# SCH_esp32_sensors_2026-04-30.net
KiCad netlist of a schematic drawn in EasyEDA
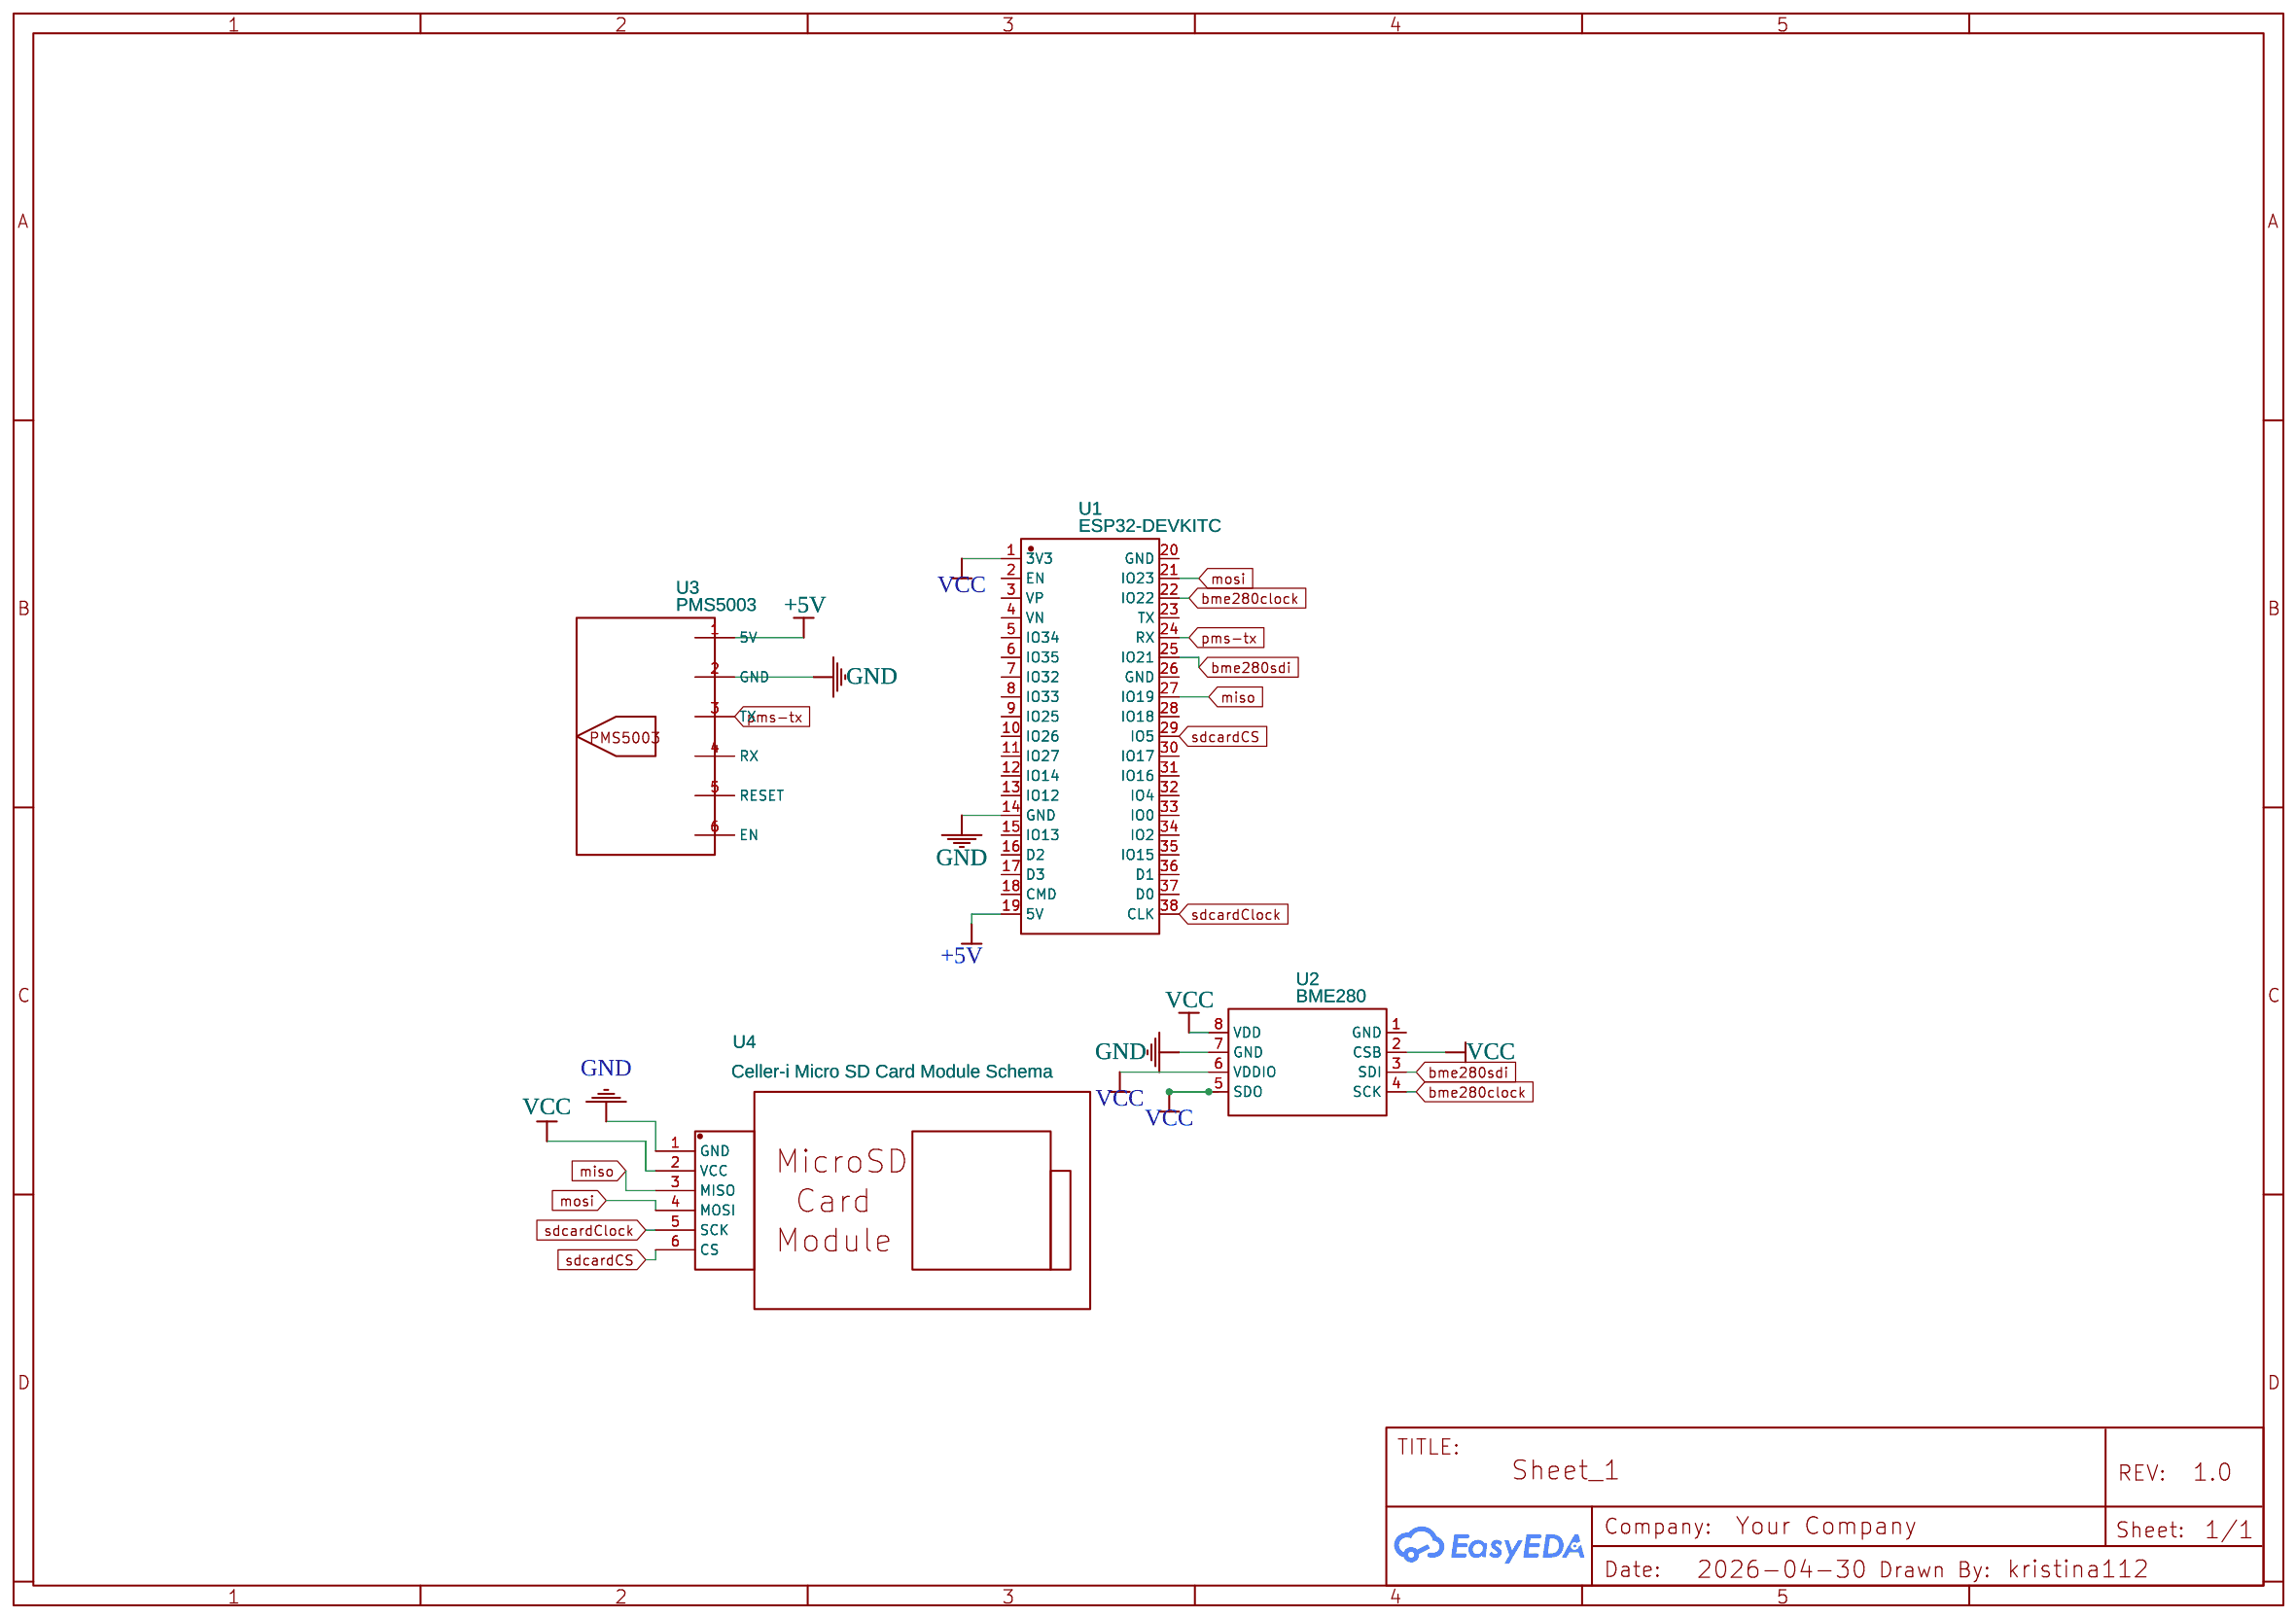
[diagram p0: schematic sheet]

(export (version "E")
  (design (tool "Eeschema 10.0.6"))
  (components
    (comp (ref "U1")
      (value "ESP32-DEVKITC")
      (fields
        (field (name "Manufacturer Part") "ESP32-DevKitC")
        (field (name "Manufacturer") "ESPRESSIF(乐鑫)")
      )
      (libsource (lib "") (part "ESP32-DEVKITC"))
    )
    (comp (ref "U2")
      (value "BME280")
      (fields (field (name "Manufacturer") "Bosch(博世)"))
      (libsource (lib "") (part "BME280"))
    )
    (comp (ref "U3") (value "PMS5003") (libsource (lib "") (part "PMS5003")))
    (comp (ref "U4")
      (value "Celler-i Micro SD Card Module Schema")
      (libsource (lib "") (part "Celler-i Micro SD Card Module Schema"))
    )
  )
  (nets
    (net (code "1") (name "+5V") (class "Default")
      (node (ref "U1") (pin "19") (pinfunction "5V_19") (pintype "unspecified"))
      (node (ref "U3") (pin "1") (pinfunction "5V_1") (pintype "unspecified"))
    )
    (net (code "2") (name "GND") (class "Default")
      (node (ref "U1") (pin "14") (pinfunction "GND_14") (pintype "unspecified"))
      (node (ref "U2") (pin "7") (pinfunction "GND_7") (pintype "unspecified"))
      (node (ref "U3") (pin "2") (pinfunction "GND_2") (pintype "unspecified"))
      (node (ref "U4") (pin "1") (pinfunction "GND_1") (pintype "unspecified"))
    )
    (net (code "3") (name "VCC") (class "Default")
      (node (ref "U1") (pin "1") (pinfunction "3V3_1") (pintype "unspecified"))
      (node (ref "U2") (pin "2") (pinfunction "CSB_2") (pintype "unspecified"))
      (node (ref "U2") (pin "5") (pinfunction "SDO_5") (pintype "unspecified"))
      (node (ref "U2") (pin "6") (pinfunction "VDDIO_6") (pintype "unspecified"))
      (node (ref "U2") (pin "8") (pinfunction "VDD_8") (pintype "unspecified"))
      (node (ref "U4") (pin "2") (pinfunction "VCC_2") (pintype "unspecified"))
    )
    (net (code "4") (name "bme280clock") (class "Default")
      (node (ref "U1") (pin "22") (pinfunction "IO22_22") (pintype "unspecified"))
      (node (ref "U2") (pin "4") (pinfunction "SCK_4") (pintype "unspecified"))
    )
    (net (code "5") (name "bme280sdi") (class "Default")
      (node (ref "U1") (pin "25") (pinfunction "IO21_25") (pintype "unspecified"))
      (node (ref "U2") (pin "3") (pinfunction "SDI_3") (pintype "unspecified"))
    )
    (net (code "6") (name "miso") (class "Default")
      (node (ref "U1") (pin "27") (pinfunction "IO19_27") (pintype "unspecified"))
      (node (ref "U4") (pin "3") (pinfunction "MISO_3") (pintype "unspecified"))
    )
    (net (code "7") (name "mosi") (class "Default")
      (node (ref "U1") (pin "21") (pinfunction "IO23_21") (pintype "unspecified"))
      (node (ref "U4") (pin "4") (pinfunction "MOSI_4") (pintype "unspecified"))
    )
    (net (code "8") (name "pms-tx") (class "Default")
      (node (ref "U1") (pin "24") (pinfunction "RX_24") (pintype "unspecified"))
    )
    (net (code "9") (name "sdcardCS") (class "Default")
      (node (ref "U1") (pin "29") (pinfunction "IO5_29") (pintype "unspecified"))
      (node (ref "U4") (pin "6") (pinfunction "CS_6") (pintype "unspecified"))
    )
    (net (code "10") (name "sdcardClock") (class "Default")
      (node (ref "U1") (pin "38") (pinfunction "CLK_38") (pintype "unspecified"))
      (node (ref "U4") (pin "5") (pinfunction "SCK_5") (pintype "unspecified"))
    )
    (net (code "11") (name "unconnected-(U1-CMD-Pad18)") (class "Default")
      (node (ref "U1") (pin "18") (pinfunction "CMD_18") (pintype "unspecified"))
    )
    (net (code "12") (name "unconnected-(U1-D0-Pad37)") (class "Default")
      (node (ref "U1") (pin "37") (pinfunction "D0_37") (pintype "unspecified"))
    )
    (net (code "13") (name "unconnected-(U1-D1-Pad36)") (class "Default")
      (node (ref "U1") (pin "36") (pinfunction "D1_36") (pintype "unspecified"))
    )
    (net (code "14") (name "unconnected-(U1-D2-Pad16)") (class "Default")
      (node (ref "U1") (pin "16") (pinfunction "D2_16") (pintype "unspecified"))
    )
    (net (code "15") (name "unconnected-(U1-D3-Pad17)") (class "Default")
      (node (ref "U1") (pin "17") (pinfunction "D3_17") (pintype "unspecified"))
    )
    (net (code "16") (name "unconnected-(U1-EN-Pad2)") (class "Default")
      (node (ref "U1") (pin "2") (pinfunction "EN_2") (pintype "unspecified"))
    )
    (net (code "17") (name "unconnected-(U1-GND-Pad20)") (class "Default")
      (node (ref "U1") (pin "20") (pinfunction "GND_20") (pintype "unspecified"))
    )
    (net (code "18") (name "unconnected-(U1-GND-Pad26)") (class "Default")
      (node (ref "U1") (pin "26") (pinfunction "GND_26") (pintype "unspecified"))
    )
    (net (code "19") (name "unconnected-(U1-IO0-Pad33)") (class "Default")
      (node (ref "U1") (pin "33") (pinfunction "IO0_33") (pintype "unspecified"))
    )
    (net (code "20") (name "unconnected-(U1-IO2-Pad34)") (class "Default")
      (node (ref "U1") (pin "34") (pinfunction "IO2_34") (pintype "unspecified"))
    )
    (net (code "21") (name "unconnected-(U1-IO4-Pad32)") (class "Default")
      (node (ref "U1") (pin "32") (pinfunction "IO4_32") (pintype "unspecified"))
    )
    (net (code "22") (name "unconnected-(U1-IO12-Pad13)") (class "Default")
      (node (ref "U1") (pin "13") (pinfunction "IO12_13") (pintype "unspecified"))
    )
    (net (code "23") (name "unconnected-(U1-IO13-Pad15)") (class "Default")
      (node (ref "U1") (pin "15") (pinfunction "IO13_15") (pintype "unspecified"))
    )
    (net (code "24") (name "unconnected-(U1-IO14-Pad12)") (class "Default")
      (node (ref "U1") (pin "12") (pinfunction "IO14_12") (pintype "unspecified"))
    )
    (net (code "25") (name "unconnected-(U1-IO15-Pad35)") (class "Default")
      (node (ref "U1") (pin "35") (pinfunction "IO15_35") (pintype "unspecified"))
    )
    (net (code "26") (name "unconnected-(U1-IO16-Pad31)") (class "Default")
      (node (ref "U1") (pin "31") (pinfunction "IO16_31") (pintype "unspecified"))
    )
    (net (code "27") (name "unconnected-(U1-IO17-Pad30)") (class "Default")
      (node (ref "U1") (pin "30") (pinfunction "IO17_30") (pintype "unspecified"))
    )
    (net (code "28") (name "unconnected-(U1-IO18-Pad28)") (class "Default")
      (node (ref "U1") (pin "28") (pinfunction "IO18_28") (pintype "unspecified"))
    )
    (net (code "29") (name "unconnected-(U1-IO25-Pad9)") (class "Default")
      (node (ref "U1") (pin "9") (pinfunction "IO25_9") (pintype "unspecified"))
    )
    (net (code "30") (name "unconnected-(U1-IO26-Pad10)") (class "Default")
      (node (ref "U1") (pin "10") (pinfunction "IO26_10") (pintype "unspecified"))
    )
    (net (code "31") (name "unconnected-(U1-IO27-Pad11)") (class "Default")
      (node (ref "U1") (pin "11") (pinfunction "IO27_11") (pintype "unspecified"))
    )
    (net (code "32") (name "unconnected-(U1-IO32-Pad7)") (class "Default")
      (node (ref "U1") (pin "7") (pinfunction "IO32_7") (pintype "unspecified"))
    )
    (net (code "33") (name "unconnected-(U1-IO33-Pad8)") (class "Default")
      (node (ref "U1") (pin "8") (pinfunction "IO33_8") (pintype "unspecified"))
    )
    (net (code "34") (name "unconnected-(U1-IO34-Pad5)") (class "Default")
      (node (ref "U1") (pin "5") (pinfunction "IO34_5") (pintype "unspecified"))
    )
    (net (code "35") (name "unconnected-(U1-IO35-Pad6)") (class "Default")
      (node (ref "U1") (pin "6") (pinfunction "IO35_6") (pintype "unspecified"))
    )
    (net (code "36") (name "unconnected-(U1-TX-Pad23)") (class "Default")
      (node (ref "U1") (pin "23") (pinfunction "TX_23") (pintype "unspecified"))
    )
    (net (code "37") (name "unconnected-(U1-VN-Pad4)") (class "Default")
      (node (ref "U1") (pin "4") (pinfunction "VN_4") (pintype "unspecified"))
    )
    (net (code "38") (name "unconnected-(U1-VP-Pad3)") (class "Default")
      (node (ref "U1") (pin "3") (pinfunction "VP_3") (pintype "unspecified"))
    )
    (net (code "39") (name "unconnected-(U2-GND-Pad1)") (class "Default")
      (node (ref "U2") (pin "1") (pinfunction "GND_1") (pintype "unspecified"))
    )
    (net (code "40") (name "unconnected-(U3-EN-Pad6)") (class "Default")
      (node (ref "U3") (pin "6") (pinfunction "EN_6") (pintype "unspecified"))
    )
    (net (code "41") (name "unconnected-(U3-RESET-Pad5)") (class "Default")
      (node (ref "U3") (pin "5") (pinfunction "RESET_5") (pintype "unspecified"))
    )
    (net (code "42") (name "unconnected-(U3-RX-Pad4)") (class "Default")
      (node (ref "U3") (pin "4") (pinfunction "RX_4") (pintype "unspecified"))
    )
    (net (code "43") (name "unconnected-(U3-TX-Pad3)") (class "Default")
      (node (ref "U3") (pin "3") (pinfunction "TX_3") (pintype "unspecified"))
    )
  )
)
